# blink1mk3_micro1c.net
KiCad netlist of a schematic drawn in EAGLE
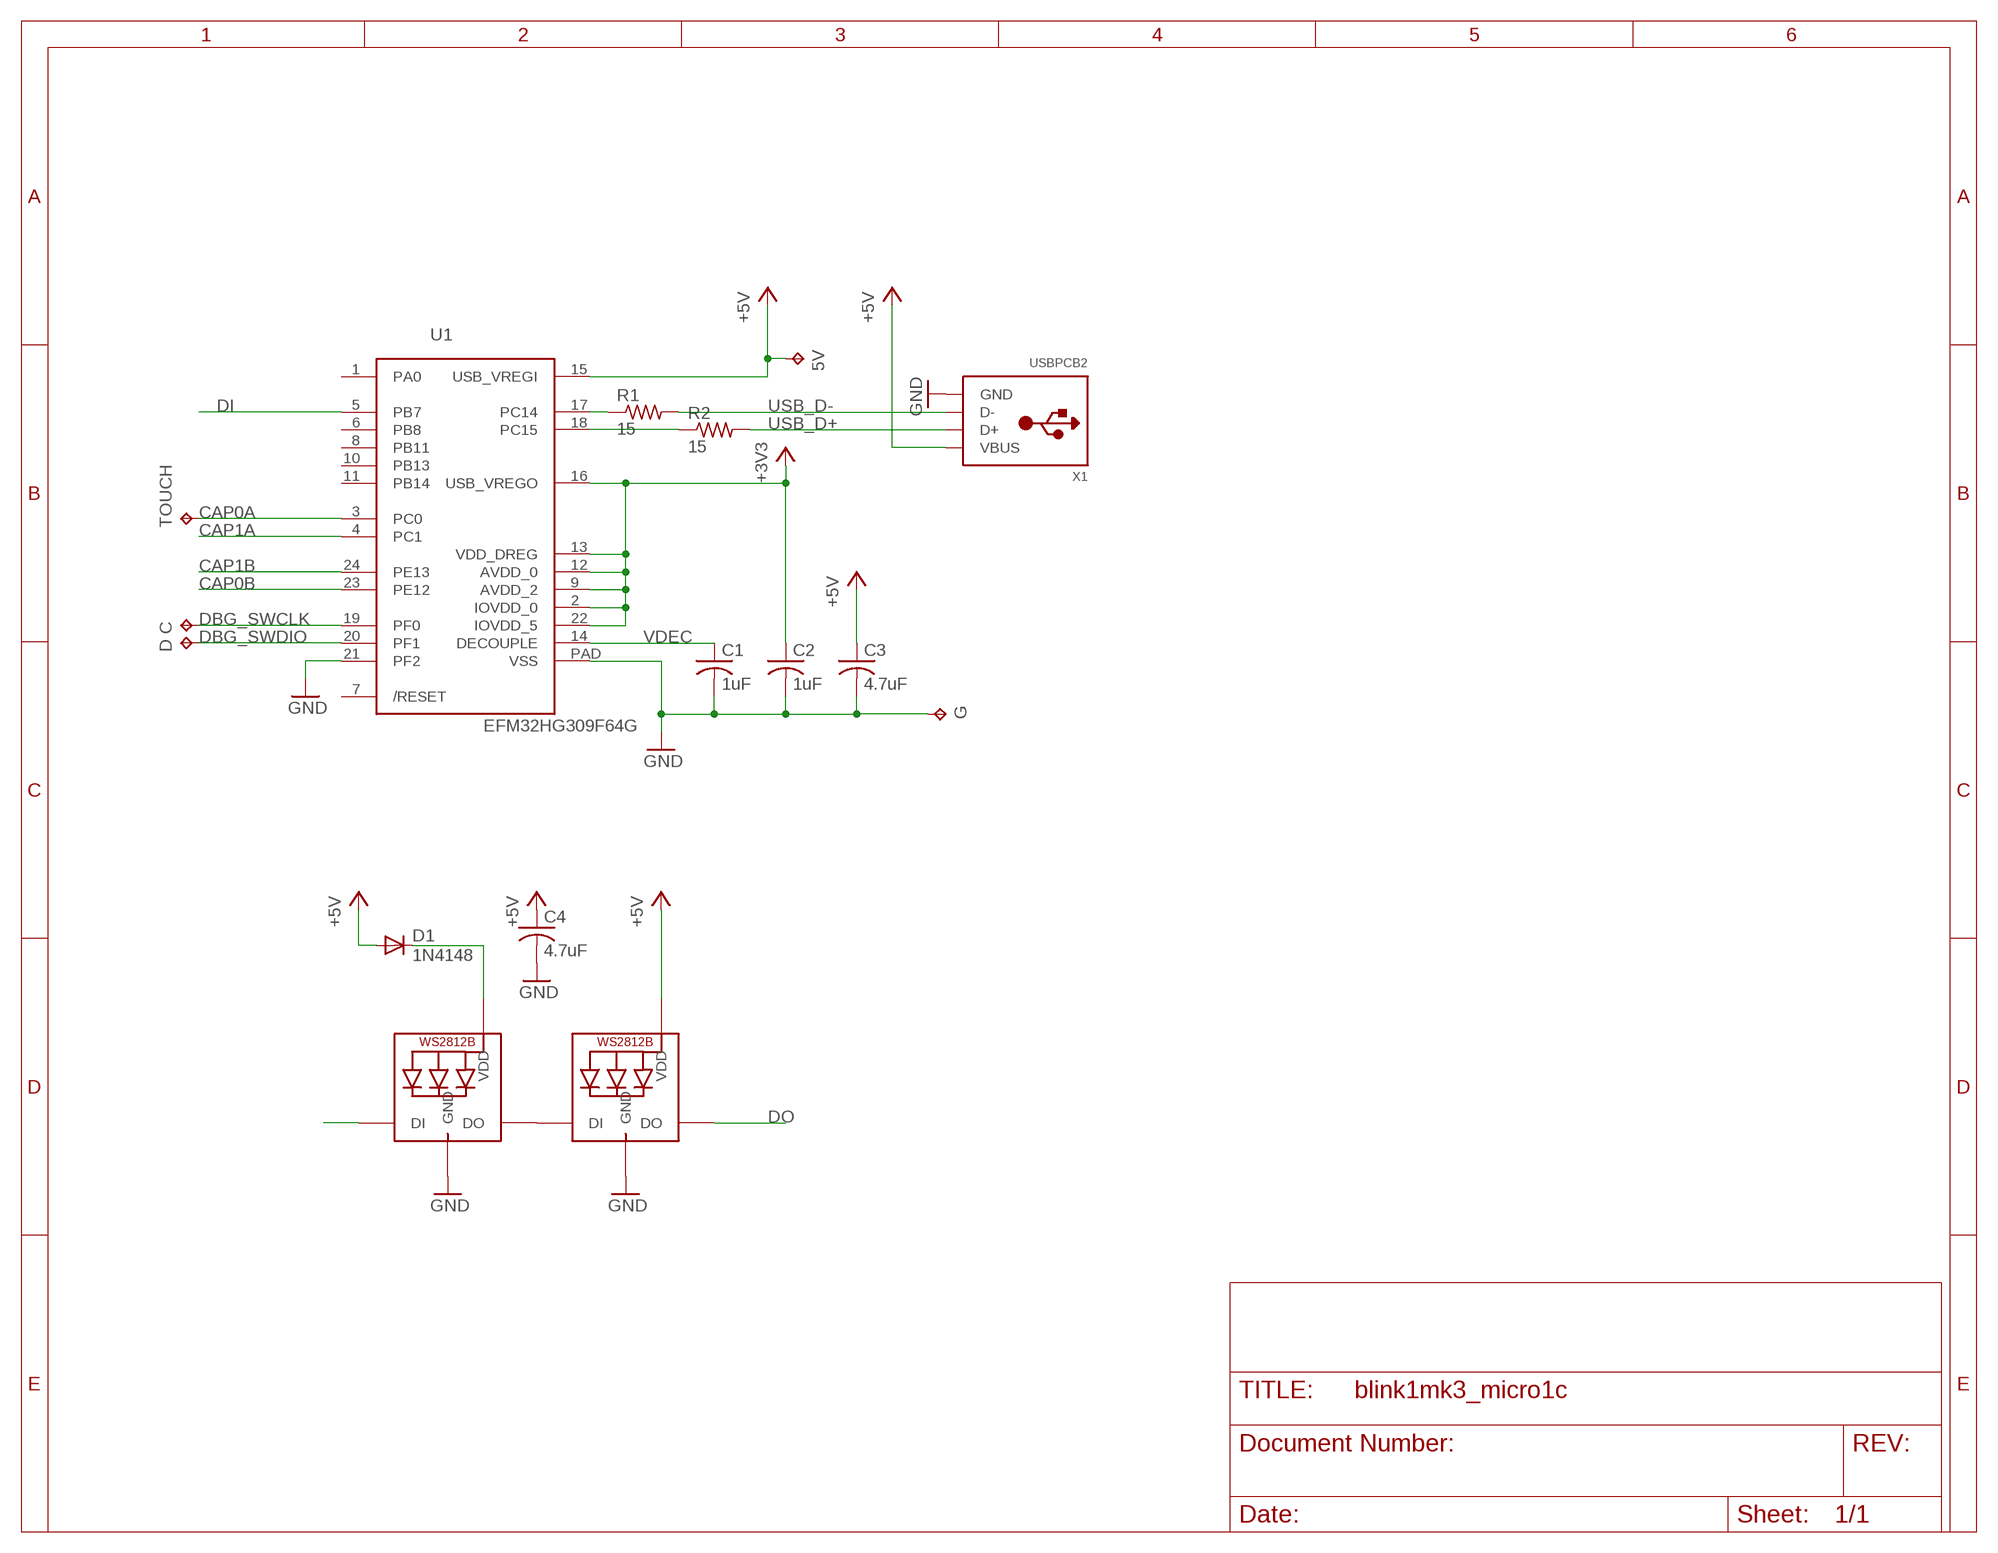
[diagram p0: schematic, sheet 1]

(export (version "E")
  (design (tool "Eeschema 10.0.6"))
  (components
    (comp (ref "5V")
      (value "TPTP10R")
      (footprint "eagle-import:TP10R")
      (libsource (lib "eagle-import") (part "TPTP10R"))
    )
    (comp (ref "C")
      (value "TPTP10R")
      (footprint "eagle-import:TP10R")
      (libsource (lib "eagle-import") (part "TPTP10R"))
    )
    (comp (ref "C1")
      (value "1uF")
      (footprint "eagle-import:C0402")
      (libsource (lib "eagle-import") (part "C-USC0402"))
    )
    (comp (ref "C2")
      (value "1uF")
      (footprint "eagle-import:C0402")
      (libsource (lib "eagle-import") (part "C-USC0402"))
    )
    (comp (ref "C3")
      (value "4.7uF")
      (footprint "eagle-import:C0402")
      (libsource (lib "eagle-import") (part "C-USC0402"))
    )
    (comp (ref "C4")
      (value "4.7uF")
      (footprint "eagle-import:C0402")
      (libsource (lib "eagle-import") (part "C-USC0402"))
    )
    (comp (ref "D")
      (value "TPTP10R")
      (footprint "eagle-import:TP10R")
      (libsource (lib "eagle-import") (part "TPTP10R"))
    )
    (comp (ref "D1")
      (value "1N4148")
      (footprint "eagle-import:SOD523")
      (libsource (lib "eagle-import") (part "DIODE-SOD523"))
    )
    (comp (ref "G")
      (value "TPTP10SQ")
      (footprint "eagle-import:TP10SQ")
      (libsource (lib "eagle-import") (part "TPTP10SQ"))
    )
    (comp (ref "LED1")
      (value "WS2812B4020SIDE")
      (footprint "eagle-import:SK6812-SIDE")
      (libsource (lib "eagle-import") (part "WS2812B4020SIDE"))
    )
    (comp (ref "LED2")
      (value "WS2812B4020SIDE")
      (footprint "eagle-import:SK6812-SIDE")
      (libsource (lib "eagle-import") (part "WS2812B4020SIDE"))
    )
    (comp (ref "R1")
      (value "15")
      (footprint "eagle-import:R0402")
      (libsource (lib "eagle-import") (part "R-US_R0402"))
    )
    (comp (ref "R2")
      (value "15")
      (footprint "eagle-import:R0402")
      (libsource (lib "eagle-import") (part "R-US_R0402"))
    )
    (comp (ref "TOUCH")
      (value "TPTP10R")
      (footprint "eagle-import:TP10R")
      (libsource (lib "eagle-import") (part "TPTP10R"))
    )
    (comp (ref "U1")
      (value "EFM32HG309F64G")
      (footprint "eagle-import:QFN24PAD")
      (libsource (lib "eagle-import") (part "EFM32HG309F64G"))
    )
    (comp (ref "X1")
      (value "USBPCB2")
      (footprint "eagle-import:USB-A-PCB-2")
      (libsource (lib "eagle-import") (part "USBPCB2"))
    )
  )
  (nets
    (net (code "1") (name "+3V3") (class "Default")
      (node (ref "C2") (pin "1") (pinfunction "1_1") (pintype "passive"))
      (node (ref "U1") (pin "12") (pinfunction "AVDD_0_12") (pintype "bidirectional"))
      (node (ref "U1") (pin "13") (pinfunction "VDD_DREG_13") (pintype "bidirectional"))
      (node (ref "U1") (pin "16") (pinfunction "USB_VREGO_16") (pintype "bidirectional"))
      (node (ref "U1") (pin "2") (pinfunction "IOVDD_0_2") (pintype "bidirectional"))
      (node (ref "U1") (pin "22") (pinfunction "IOVDD_5_22") (pintype "bidirectional"))
      (node (ref "U1") (pin "9") (pinfunction "AVDD_2_9") (pintype "bidirectional"))
    )
    (net (code "2") (name "+5V") (class "Default")
      (node (ref "5V") (pin "TP") (pinfunction "TP_TP") (pintype "input"))
      (node (ref "C3") (pin "1") (pinfunction "1_1") (pintype "passive"))
      (node (ref "C4") (pin "1") (pinfunction "1_1") (pintype "passive"))
      (node (ref "D1") (pin "A") (pinfunction "A_A") (pintype "passive"))
      (node (ref "LED2") (pin "1-VDD") (pinfunction "VDD_1-VDD") (pintype "power_in"))
      (node (ref "U1") (pin "15") (pinfunction "USB_VREGI_15") (pintype "bidirectional"))
      (node (ref "X1") (pin "5V") (pinfunction "VBUS_5V") (pintype "power_in"))
    )
    (net (code "3") (name "/CAP0A") (class "Default")
      (node (ref "TOUCH") (pin "TP") (pinfunction "TP_TP") (pintype "input"))
      (node (ref "U1") (pin "3") (pinfunction "PC0_3") (pintype "bidirectional"))
    )
    (net (code "4") (name "/CAP0B") (class "Default")
      (node (ref "U1") (pin "23") (pinfunction "PE12_23") (pintype "bidirectional"))
    )
    (net (code "5") (name "/CAP1A") (class "Default")
      (node (ref "U1") (pin "4") (pinfunction "PC1_4") (pintype "bidirectional"))
    )
    (net (code "6") (name "/CAP1B") (class "Default")
      (node (ref "U1") (pin "24") (pinfunction "PE13_24") (pintype "bidirectional"))
    )
    (net (code "7") (name "/DBG_SWCLK") (class "Default")
      (node (ref "C") (pin "TP") (pinfunction "TP_TP") (pintype "input"))
      (node (ref "U1") (pin "19") (pinfunction "PF0_19") (pintype "bidirectional"))
    )
    (net (code "8") (name "/DBG_SWDIO") (class "Default")
      (node (ref "D") (pin "TP") (pinfunction "TP_TP") (pintype "input"))
      (node (ref "U1") (pin "20") (pinfunction "PF1_20") (pintype "bidirectional"))
    )
    (net (code "9") (name "/DI") (class "Default")
      (node (ref "LED1") (pin "4-DIN") (pinfunction "DI_4-DIN") (pintype "input"))
      (node (ref "U1") (pin "5") (pinfunction "PB7_5") (pintype "bidirectional"))
    )
    (net (code "10") (name "/DO") (class "Default")
      (node (ref "LED2") (pin "2-DOUT") (pinfunction "DO_2-DOUT") (pintype "output"))
    )
    (net (code "11") (name "/USB_D+") (class "Default")
      (node (ref "R2") (pin "2") (pinfunction "2_2") (pintype "passive"))
      (node (ref "X1") (pin "USB_P") (pinfunction "D+_USB_P") (pintype "bidirectional"))
    )
    (net (code "12") (name "/USB_D-") (class "Default")
      (node (ref "R1") (pin "2") (pinfunction "2_2") (pintype "passive"))
      (node (ref "X1") (pin "USB_M") (pinfunction "D-_USB_M") (pintype "bidirectional"))
    )
    (net (code "13") (name "/VDEC") (class "Default")
      (node (ref "C1") (pin "1") (pinfunction "1_1") (pintype "passive"))
      (node (ref "U1") (pin "14") (pinfunction "DECOUPLE_14") (pintype "bidirectional"))
    )
    (net (code "14") (name "GND") (class "Default")
      (node (ref "C1") (pin "2") (pinfunction "2_2") (pintype "passive"))
      (node (ref "C2") (pin "2") (pinfunction "2_2") (pintype "passive"))
      (node (ref "C3") (pin "2") (pinfunction "2_2") (pintype "passive"))
      (node (ref "C4") (pin "2") (pinfunction "2_2") (pintype "passive"))
      (node (ref "G") (pin "TP") (pinfunction "TP_TP") (pintype "input"))
      (node (ref "LED1") (pin "3-GND") (pinfunction "GND_3-GND") (pintype "power_in"))
      (node (ref "LED2") (pin "3-GND") (pinfunction "GND_3-GND") (pintype "power_in"))
      (node (ref "U1") (pin "21") (pinfunction "PF2_21") (pintype "bidirectional"))
      (node (ref "U1") (pin "PAD") (pinfunction "VSS_PAD") (pintype "bidirectional"))
      (node (ref "X1") (pin "GND") (pinfunction "GND_GND") (pintype "power_in"))
    )
    (net (code "15") (name "Net-(LED1-DO)") (class "Default")
      (node (ref "LED1") (pin "2-DOUT") (pinfunction "DO_2-DOUT") (pintype "output"))
      (node (ref "LED2") (pin "4-DIN") (pinfunction "DI_4-DIN") (pintype "input"))
    )
    (net (code "16") (name "Net-(LED1-VDD)") (class "Default")
      (node (ref "D1") (pin "C") (pinfunction "C_C") (pintype "passive"))
      (node (ref "LED1") (pin "1-VDD") (pinfunction "VDD_1-VDD") (pintype "power_in"))
    )
    (net (code "17") (name "Net-(U1-PC14)") (class "Default")
      (node (ref "R1") (pin "1") (pinfunction "1_1") (pintype "passive"))
      (node (ref "U1") (pin "17") (pinfunction "PC14_17") (pintype "bidirectional"))
    )
    (net (code "18") (name "Net-(U1-PC15)") (class "Default")
      (node (ref "R2") (pin "1") (pinfunction "1_1") (pintype "passive"))
      (node (ref "U1") (pin "18") (pinfunction "PC15_18") (pintype "bidirectional"))
    )
    (net (code "19") (name "unconnected-(U1-PA0-Pad1)") (class "Default")
      (node (ref "U1") (pin "1") (pinfunction "PA0_1") (pintype "bidirectional"))
    )
    (net (code "20") (name "unconnected-(U1-PB8-Pad6)") (class "Default")
      (node (ref "U1") (pin "6") (pinfunction "PB8_6") (pintype "bidirectional"))
    )
    (net (code "21") (name "unconnected-(U1-PB11-Pad8)") (class "Default")
      (node (ref "U1") (pin "8") (pinfunction "PB11_8") (pintype "bidirectional"))
    )
    (net (code "22") (name "unconnected-(U1-PB13-Pad10)") (class "Default")
      (node (ref "U1") (pin "10") (pinfunction "PB13_10") (pintype "bidirectional"))
    )
    (net (code "23") (name "unconnected-(U1-PB14-Pad11)") (class "Default")
      (node (ref "U1") (pin "11") (pinfunction "PB14_11") (pintype "bidirectional"))
    )
    (net (code "24") (name "unconnected-(U1-{slash}RESET-Pad7)") (class "Default")
      (node (ref "U1") (pin "7") (pinfunction "/RESET_7") (pintype "bidirectional"))
    )
  )
)
